# heaters.net
KiCad netlist of a schematic drawn in Altium Designer
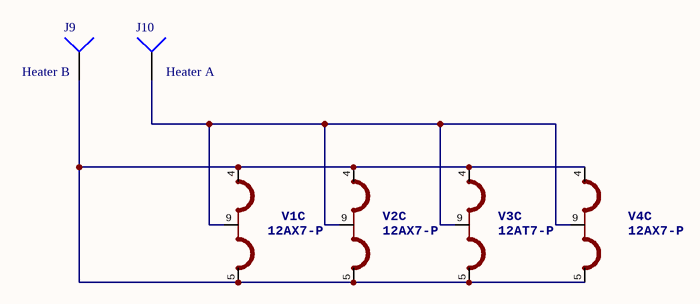
[diagram p0: heaters.SchDoc]

(export (version "E")
  (design (tool "Eeschema 10.0.6"))
  (components
    (comp (ref "J9")
      (value "Heater B")
      (footprint "PIN1")
      (description "Socket")
      (fields (field (name "PUBLISHER") "Altium Limited"))
      (libsource (lib "Miscellaneous Connectors") (part "Socket"))
    )
    (comp (ref "J10")
      (value "Heater A")
      (footprint "PIN1")
      (description "Socket")
      (fields (field (name "PUBLISHER") "Altium Limited"))
      (libsource (lib "Miscellaneous Connectors") (part "Socket"))
    )
    (comp (ref "V1")
      (value "12AX7-P")
      (footprint "NOVAL")
      (libsource (lib "eagle_tubes_v6") (part "12AX7-P"))
    )
    (comp (ref "V2")
      (value "12AX7-P")
      (footprint "NOVAL")
      (libsource (lib "eagle_tubes_v6") (part "12AX7-P"))
    )
    (comp (ref "V3")
      (value "12AT7-P")
      (footprint "NOVAL")
      (libsource (lib "eagle_tubes_v6") (part "12AT7-P"))
    )
    (comp (ref "V4")
      (value "12AX7-P")
      (footprint "NOVAL")
      (libsource (lib "eagle_tubes_v6") (part "12AX7-P"))
    )
  )
  (nets
    (net (code "1") (name "Net-(V1C-H1)") (class "Default")
      (node (ref "J9") (pin "1") (pinfunction "1_1") (pintype "passive"))
      (node (ref "V1") (pin "4") (pinfunction "H1_4") (pintype "passive"))
      (node (ref "V1") (pin "5") (pinfunction "H3_5") (pintype "passive"))
      (node (ref "V2") (pin "4") (pinfunction "H1_4") (pintype "passive"))
      (node (ref "V2") (pin "5") (pinfunction "H3_5") (pintype "passive"))
      (node (ref "V3") (pin "4") (pinfunction "H1_4") (pintype "passive"))
      (node (ref "V3") (pin "5") (pinfunction "H3_5") (pintype "passive"))
      (node (ref "V4") (pin "4") (pinfunction "H1_4") (pintype "passive"))
      (node (ref "V4") (pin "5") (pinfunction "H3_5") (pintype "passive"))
    )
    (net (code "2") (name "Net-(V1C-H2)") (class "Default")
      (node (ref "J10") (pin "1") (pinfunction "1_1") (pintype "passive"))
      (node (ref "V1") (pin "9") (pinfunction "H2_9") (pintype "passive"))
      (node (ref "V2") (pin "9") (pinfunction "H2_9") (pintype "passive"))
      (node (ref "V3") (pin "9") (pinfunction "H2_9") (pintype "passive"))
      (node (ref "V4") (pin "9") (pinfunction "H2_9") (pintype "passive"))
    )
  )
)
